# nexa_remote.net
KiCad netlist of a schematic drawn in EAGLE
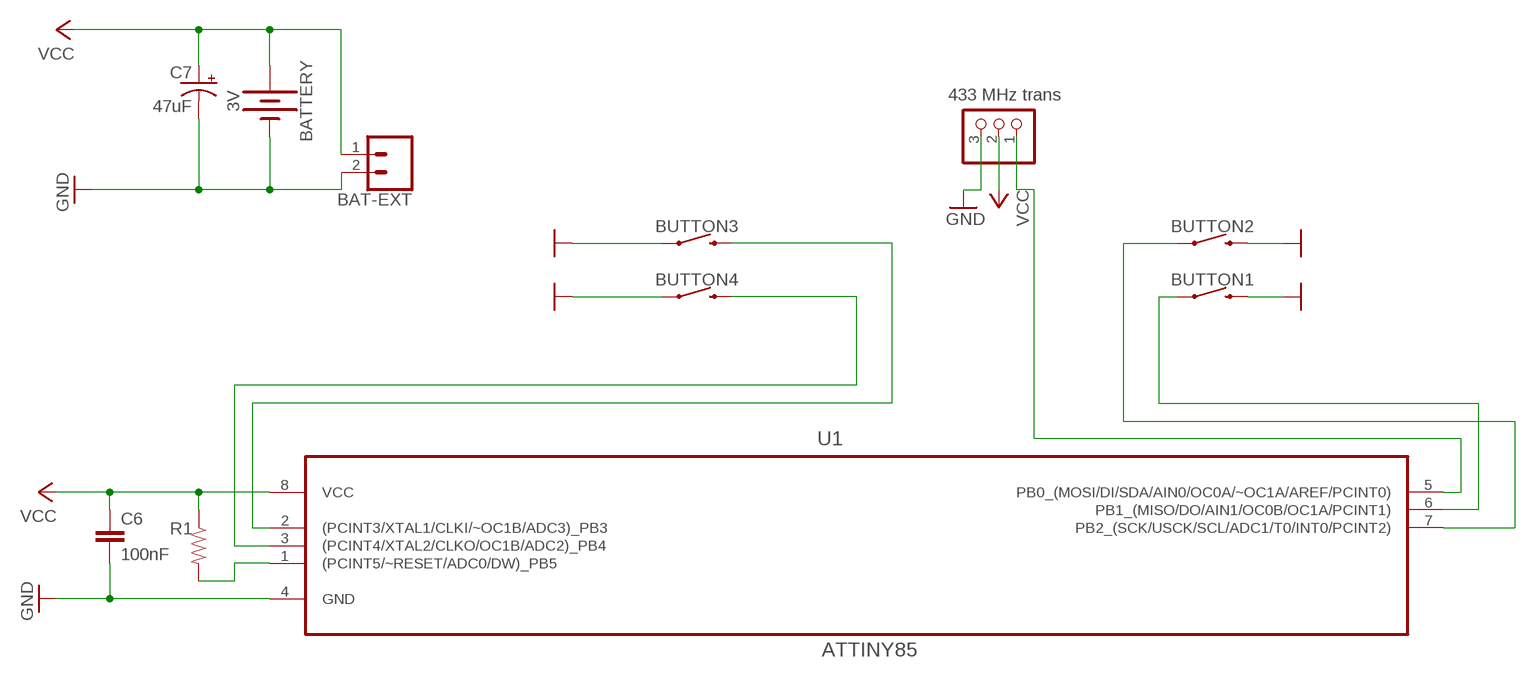
[diagram p0: schematic, sheet 1]

(export (version "E")
  (design (tool "Eeschema 10.0.6"))
  (components
    (comp (ref "BAT-EXT")
      (value "CONN_023.5MM")
      (footprint "eagle-import:SCREWTERMINAL-3.5MM-2")
      (libsource (lib "eagle-import") (part "CONN_023.5MM"))
    )
    (comp (ref "BATTERY")
      (value "3V")
      (footprint "eagle-import:BATTCON_20MM_4LEGS")
      (libsource (lib "eagle-import") (part "BATTERY-20MM_SMD_4LEGS"))
    )
    (comp (ref "BUTTON1")
      (value "MOMENTARY-SWITCH-SPST-PTH-6.0MM")
      (footprint "eagle-import:TACTILE_SWITCH_PTH_6.0MM")
      (libsource (lib "eagle-import") (part "MOMENTARY-SWITCH-SPST-PTH-6.0MM"))
    )
    (comp (ref "BUTTON2")
      (value "MOMENTARY-SWITCH-SPST-PTH-6.0MM")
      (footprint "eagle-import:TACTILE_SWITCH_PTH_6.0MM")
      (libsource (lib "eagle-import") (part "MOMENTARY-SWITCH-SPST-PTH-6.0MM"))
    )
    (comp (ref "BUTTON3")
      (value "MOMENTARY-SWITCH-SPST-PTH-6.0MM")
      (footprint "eagle-import:TACTILE_SWITCH_PTH_6.0MM")
      (libsource (lib "eagle-import") (part "MOMENTARY-SWITCH-SPST-PTH-6.0MM"))
    )
    (comp (ref "BUTTON4")
      (value "MOMENTARY-SWITCH-SPST-PTH-6.0MM")
      (footprint "eagle-import:TACTILE_SWITCH_PTH_6.0MM")
      (libsource (lib "eagle-import") (part "MOMENTARY-SWITCH-SPST-PTH-6.0MM"))
    )
    (comp (ref "C6")
      (value "100nF")
      (footprint "eagle-import:0805")
      (libsource (lib "eagle-import") (part "0.33UF/330NF-0805-50V-10%"))
    )
    (comp (ref "C7")
      (value "47uF")
      (footprint "eagle-import:CPOL-RADIAL-2.5MM-5MM")
      (libsource (lib "eagle-import") (part "10UF-POLAR-RADIAL-2.5MM-25V-20%"))
    )
    (comp (ref "JMR-TX-1")
      (value "433 MHz trans")
      (footprint "eagle-import:1X03-CLEANBIG")
      (libsource (lib "eagle-import") (part "PINHD-1X3CB"))
    )
    (comp (ref "R1")
      (value "10K")
      (footprint "eagle-import:0805")
      (libsource (lib "eagle-import") (part "0.3OHM-0805-1/8W-1%"))
    )
    (comp (ref "U1")
      (value "ATTINY85")
      (footprint "eagle-import:DIP254P762X533-8")
      (fields (field (name "MPN") "ATTINY85-20PU"))
      (libsource (lib "eagle-import") (part "ATTINY85-20PU"))
    )
  )
  (nets
    (net (code "1") (name "GND") (class "Default")
      (node (ref "BAT-EXT") (pin "2") (pinfunction "2_2") (pintype "passive"))
      (node (ref "BATTERY") (pin "NEGATIVE") (pinfunction "-_NEGATIVE") (pintype "power_in"))
      (node (ref "BUTTON1") (pin "3") (pinfunction "2_3") (pintype "passive"))
      (node (ref "BUTTON2") (pin "3") (pinfunction "2_3") (pintype "passive"))
      (node (ref "BUTTON3") (pin "1") (pinfunction "1_1") (pintype "passive"))
      (node (ref "BUTTON4") (pin "1") (pinfunction "1_1") (pintype "passive"))
      (node (ref "C6") (pin "2") (pinfunction "2_2") (pintype "passive"))
      (node (ref "C7") (pin "2") (pinfunction "-_2") (pintype "passive"))
      (node (ref "JMR-TX-1") (pin "3") (pinfunction "3_3") (pintype "passive"))
      (node (ref "U1") (pin "4") (pinfunction "GND_4") (pintype "passive"))
    )
    (net (code "2") (name "Net-(BUTTON3-2)") (class "Default")
      (node (ref "BUTTON3") (pin "3") (pinfunction "2_3") (pintype "passive"))
      (node (ref "U1") (pin "2") (pinfunction "(PCINT3/XTAL1/CLKI/~{OC1B/ADC3})_PB3_2") (pintype "bidirectional"))
    )
    (net (code "3") (name "Net-(BUTTON4-2)") (class "Default")
      (node (ref "BUTTON4") (pin "3") (pinfunction "2_3") (pintype "passive"))
      (node (ref "U1") (pin "3") (pinfunction "(PCINT4/XTAL2/CLKO/OC1B/ADC2)_PB4_3") (pintype "bidirectional"))
    )
    (net (code "4") (name "Net-(U1-(PCINT5{slash}~{RESET{slash}ADC0{slash}DW})_PB5)") (class "Default")
      (node (ref "R1") (pin "2") (pinfunction "2_2") (pintype "passive"))
      (node (ref "U1") (pin "1") (pinfunction "(PCINT5/~{RESET/ADC0/DW})_PB5_1") (pintype "bidirectional"))
    )
    (net (code "5") (name "Net-(U1-PB0_(MOSI{slash}DI{slash}SDA{slash}AIN0{slash}OC0A{slash}~{OC1A{slash}AREF{slash}PCINT0}))") (class "Default")
      (node (ref "JMR-TX-1") (pin "1") (pinfunction "1_1") (pintype "passive"))
      (node (ref "U1") (pin "5") (pinfunction "PB0_(MOSI/DI/SDA/AIN0/OC0A/~{OC1A/AREF/PCINT0})_5") (pintype "bidirectional"))
    )
    (net (code "6") (name "Net-(U1-PB1_(MISO{slash}DO{slash}AIN1{slash}OC0B{slash}OC1A{slash}PCINT1))") (class "Default")
      (node (ref "BUTTON1") (pin "1") (pinfunction "1_1") (pintype "passive"))
      (node (ref "U1") (pin "6") (pinfunction "PB1_(MISO/DO/AIN1/OC0B/OC1A/PCINT1)_6") (pintype "bidirectional"))
    )
    (net (code "7") (name "Net-(U1-PB2_(SCK{slash}USCK{slash}SCL{slash}ADC1{slash}T0{slash}INT0{slash}PCINT2))") (class "Default")
      (node (ref "BUTTON2") (pin "1") (pinfunction "1_1") (pintype "passive"))
      (node (ref "U1") (pin "7") (pinfunction "PB2_(SCK/USCK/SCL/ADC1/T0/INT0/PCINT2)_7") (pintype "bidirectional"))
    )
    (net (code "8") (name "VCC") (class "Default")
      (node (ref "BAT-EXT") (pin "1") (pinfunction "1_1") (pintype "passive"))
      (node (ref "BATTERY") (pin "POSITIVE@1") (pinfunction "+_POSITIVE@1") (pintype "power_in"))
      (node (ref "BATTERY") (pin "POSITIVE@2") (pinfunction "+_POSITIVE@2") (pintype "power_in"))
      (node (ref "BATTERY") (pin "POSITIVE@3") (pinfunction "+_POSITIVE@3") (pintype "power_in"))
      (node (ref "BATTERY") (pin "POSITIVE@4") (pinfunction "+_POSITIVE@4") (pintype "power_in"))
      (node (ref "C6") (pin "1") (pinfunction "1_1") (pintype "passive"))
      (node (ref "C7") (pin "1") (pinfunction "+_1") (pintype "passive"))
      (node (ref "JMR-TX-1") (pin "2") (pinfunction "2_2") (pintype "passive"))
      (node (ref "R1") (pin "1") (pinfunction "1_1") (pintype "passive"))
      (node (ref "U1") (pin "8") (pinfunction "VCC_8") (pintype "power_in"))
    )
  )
)
